# design.net
KiCad netlist of a schematic drawn in Altium Designer
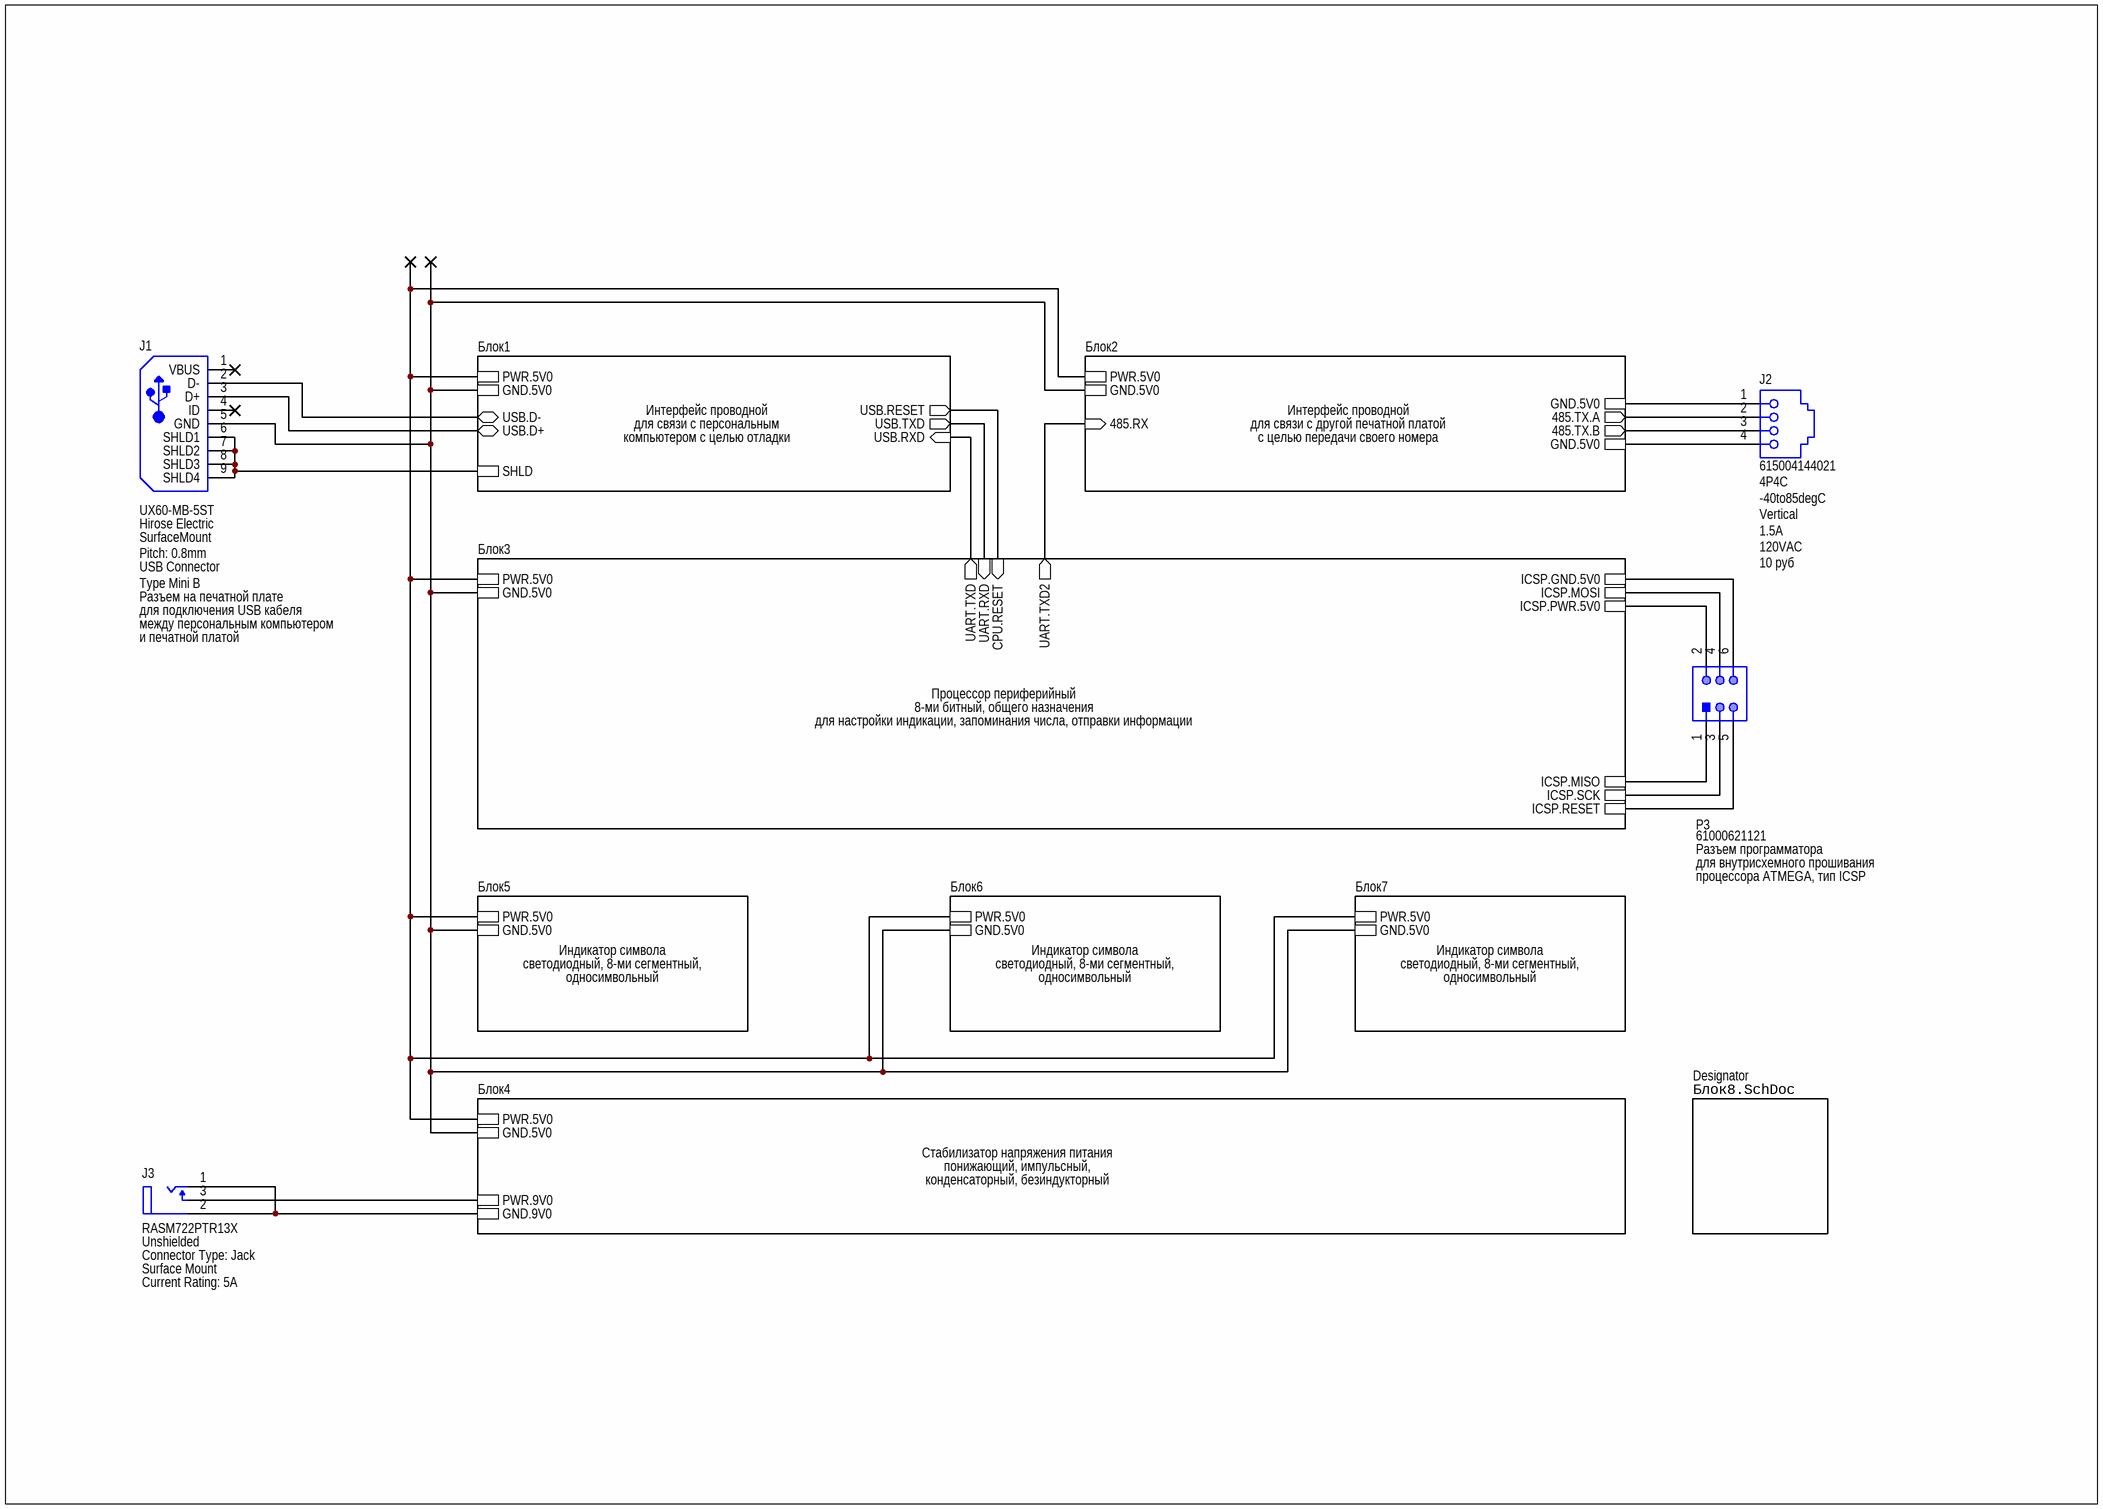
[diagram p0: Архитектура.SchDoc]

(export (version "E")
  (design (tool "Eeschema 10.0.6"))
  (components
    (comp (ref "J1")
      (value "UX60-MB-5ST")
      (footprint "HIRO-UX60-MB-5ST_V")
      (description "USB Connector Mini B Type, 1 A, 5 V AC, -30 to 75 degC, 5-Pin SMD, RoHS, Tape and Reel")
      (fields
        (field (name "MANUFACTURER") "Hirose Electric")
        (field (name "TERMINATION") "SurfaceMount")
        (field (name "PITCH") "0.8mm")
        (field (name "PARAMETER 1") "USB Connector")
        (field (name "PARAMETER 2") "Type Mini B")
        (field (name "PARAMETER 3") "Разъем на печатной плате")
        (field (name "PARAMETER 4") "для подключения USB кабеля")
        (field (name "PARAMETER 5") "между персональным компьютером")
        (field (name "PARAMETER 6") "и печатной платой")
      )
      (libsource (lib "Altium Content Vault") (part "USB-5-4SHLD"))
    )
    (comp (ref "J2")
      (value "615004144021")
      (footprint "615004144021")
      (description "Modular Jack WR-MJ, Plastic, with Panel Stop, Vertical Entry, THT, 4P4C")
      (fields
        (field (name "PIN NUMBER") "4P4C")
        (field (name "OPERATING TEMPERATURE") "-40to85degC")
        (field (name "ENTRANCE") "Vertical")
        (field (name "RATED CURRENT") "1.5A")
        (field (name "MANUFACTURER") "Wurth Elektronik")
        (field (name "WORKING VOLTAGE") "120VAC")
        (field (name "ЦЕНА") "10 руб")
        (field (name "PUBLISHER") "WurthElektronik")
      )
      (libsource (lib "Altium Content Vault") (part "WE-CN-1P-F-J4_A"))
    )
    (comp (ref "J3")
      (value "RASM722PTR13X")
      (footprint "FP-RASM722PTR13X-MFG")
      (description "CONN PWR JACK 2.1X5.5MM SOLDER")
      (fields
        (field (name "SHIELDING") "Unshielded")
        (field (name "CONNECTOR TYPE") "Jack")
        (field (name "MOUNT") "Surface Mount")
        (field (name "CURRENT RATING") "5A")
      )
      (libsource (lib "Altium Content Vault") (part "69023cd999ddc70d2a190894d9bbb58"))
    )
    (comp (ref "P3")
      (value "61000621121")
      (footprint "61000621121")
      (description "SMT Vertical Pin Header WR-PHD, Pitch 2.54 mm, Dual Row, 6 pins")
      (fields
        (field (name "MANUFACTURER") "Wurth Elektronik")
        (field (name "PARAMETER 1") "Разъем программатора")
        (field (name "PARAMETER 2") "для внутрисхемного прошивания")
        (field (name "PARAMETER 3") "процессора ATMEGA, тип ICSP")
        (field (name "PUBLISHER") "WurthElektronik")
      )
      (libsource (lib "Altium Content Vault") (part "WE-CN-2P-M-R6"))
    )
  )
  (nets
    (net (code "1") (name "/485.TX.A") (class "Default")
      (node (ref "J2") (pin "2") (pinfunction "2_2") (pintype "passive"))
    )
    (net (code "2") (name "/485.TX.B") (class "Default")
      (node (ref "J2") (pin "3") (pinfunction "3_3") (pintype "passive"))
    )
    (net (code "3") (name "/GND.5V0") (class "Default")
      (node (ref "J2") (pin "4") (pinfunction "4_4") (pintype "passive"))
    )
    (net (code "4") (name "/GND.5V0_1") (class "Default")
      (node (ref "J1") (pin "5") (pinfunction "GND_5") (pintype "power_in+no_connect"))
    )
    (net (code "5") (name "/GND.5V0_2") (class "Default")
      (node (ref "J2") (pin "1") (pinfunction "1_1") (pintype "passive"))
    )
    (net (code "6") (name "/GND.9V0") (class "Default")
      (node (ref "J3") (pin "1") (pinfunction "TIP_TERMINAL(CENTER_PIN)_1") (pintype "passive"))
      (node (ref "J3") (pin "2") (pinfunction "SLEEVE_TERMINAL_2") (pintype "passive"))
    )
    (net (code "7") (name "/ICSP.GND.5V0") (class "Default")
      (node (ref "P3") (pin "6") (pinfunction "6_6") (pintype "passive"))
    )
    (net (code "8") (name "/ICSP.MISO") (class "Default")
      (node (ref "P3") (pin "1") (pinfunction "1_1") (pintype "passive"))
    )
    (net (code "9") (name "/ICSP.MOSI") (class "Default")
      (node (ref "P3") (pin "4") (pinfunction "4_4") (pintype "passive"))
    )
    (net (code "10") (name "/ICSP.PWR.5V0") (class "Default")
      (node (ref "P3") (pin "2") (pinfunction "2_2") (pintype "passive"))
    )
    (net (code "11") (name "/ICSP.RESET") (class "Default")
      (node (ref "P3") (pin "5") (pinfunction "5_5") (pintype "passive"))
    )
    (net (code "12") (name "/ICSP.SCK") (class "Default")
      (node (ref "P3") (pin "3") (pinfunction "3_3") (pintype "passive"))
    )
    (net (code "14") (name "/PWR.9V0") (class "Default")
      (node (ref "J3") (pin "3") (pinfunction "SHUNT_TERMINAL_3") (pintype "passive"))
    )
    (net (code "15") (name "/SHLD") (class "Default")
      (node (ref "J1") (pin "6") (pinfunction "SHLD1_6") (pintype "passive"))
      (node (ref "J1") (pin "7") (pinfunction "SHLD2_7") (pintype "passive"))
      (node (ref "J1") (pin "8") (pinfunction "SHLD3_8") (pintype "passive"))
      (node (ref "J1") (pin "9") (pinfunction "SHLD4_9") (pintype "passive"))
    )
    (net (code "18") (name "/USB.D+") (class "Default")
      (node (ref "J1") (pin "3") (pinfunction "D+_3") (pintype "passive"))
    )
    (net (code "19") (name "/USB.D-") (class "Default")
      (node (ref "J1") (pin "2") (pinfunction "D-_2") (pintype "passive"))
    )
    (net (code "22") (name "unconnected-(J1-ID-Pad4)") (class "Default")
      (node (ref "J1") (pin "4") (pinfunction "ID_4") (pintype "passive+no_connect"))
    )
    (net (code "23") (name "unconnected-(J1-VBUS-Pad1)") (class "Default")
      (node (ref "J1") (pin "1") (pinfunction "VBUS_1") (pintype "power_in+no_connect"))
    )
  )
)
